# Offset.net
KiCad netlist of a schematic drawn in Altium Designer
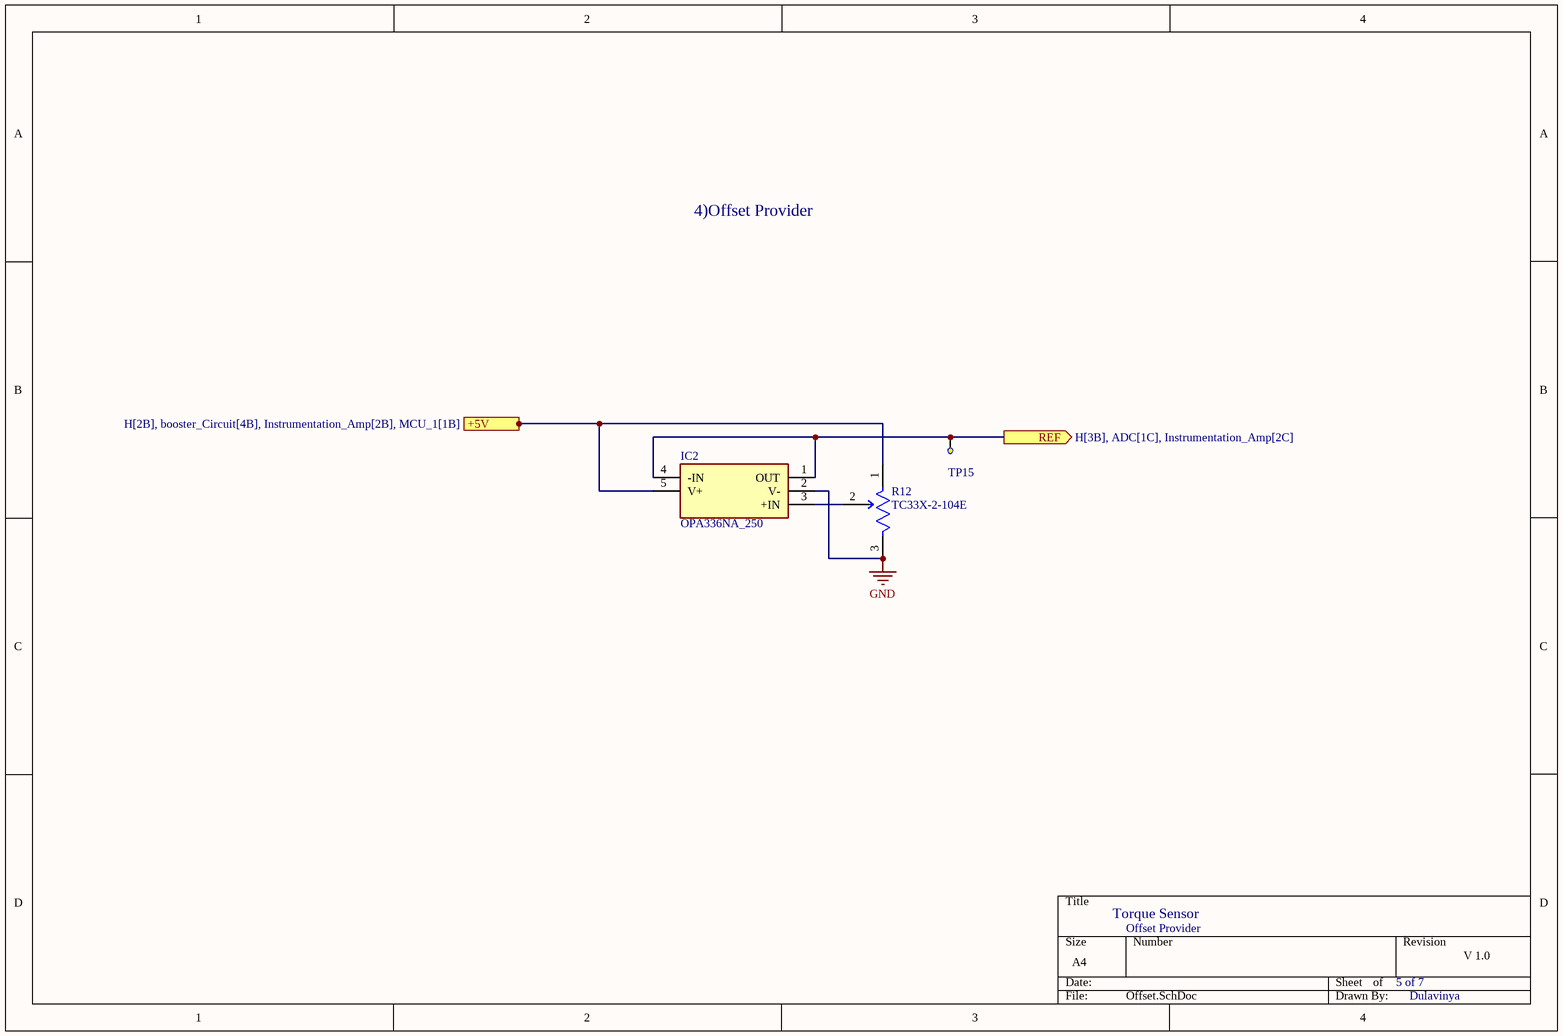
[diagram p0: Offset.SchDoc]

(export (version "E")
  (design (tool "Eeschema 10.0.6"))
  (components
    (comp (ref "IC2")
      (value "OPA336NA_250")
      (footprint "SamacSys:SOT95P280X145-5N")
      (description "Integrated Circuit")
      (fields
        (field (name "MANUFACTURER_PART_NUMBER") "OPA336NA/250")
        (field (name "MOUSER PART NUMBER") "595-OPA336NA/250")
      )
      (libsource (lib "*") (part "OPA336NA_250"))
    )
    (comp (ref "R12")
      (value "TC33X-2-104E")
      (footprint "FP-TC33X-2-MFG")
      (description "TRIMMER 100K OHM 0.1W J LEAD TOP")
      (fields (field (name "TOLERANCE") "25%"))
      (libsource (lib "Altium Content Vault") (part "13357d81287629c2fd191d242cfa50c"))
    )
    (comp (ref "TP15")
      (value "Test point")
      (footprint "Test_point")
      (libsource (lib "Schlib1") (part "test_point"))
    )
  )
  (nets
    (net (code "1") (name "/+5V") (class "Default")
      (node (ref "IC2") (pin "5") (pinfunction "V+_5") (pintype "passive"))
      (node (ref "R12") (pin "1") (pinfunction "CCW_1") (pintype "passive"))
    )
    (net (code "2") (name "/REF") (class "Default")
      (node (ref "IC2") (pin "1") (pinfunction "OUT_1") (pintype "passive"))
      (node (ref "IC2") (pin "4") (pinfunction "-IN_4") (pintype "passive"))
      (node (ref "TP15") (pin "TP?") (pinfunction "Test_point_TP?") (pintype "passive"))
    )
    (net (code "3") (name "GND") (class "Default")
      (node (ref "IC2") (pin "2") (pinfunction "V-_2") (pintype "passive"))
      (node (ref "R12") (pin "3") (pinfunction "CW_3") (pintype "passive"))
    )
    (net (code "4") (name "Net-(IC2-+IN)") (class "Default")
      (node (ref "IC2") (pin "3") (pinfunction "+IN_3") (pintype "passive"))
      (node (ref "R12") (pin "2") (pinfunction "WIPER_2") (pintype "passive"))
    )
  )
)
